# MRFM12B.net
KiCad netlist of a schematic drawn in EAGLE
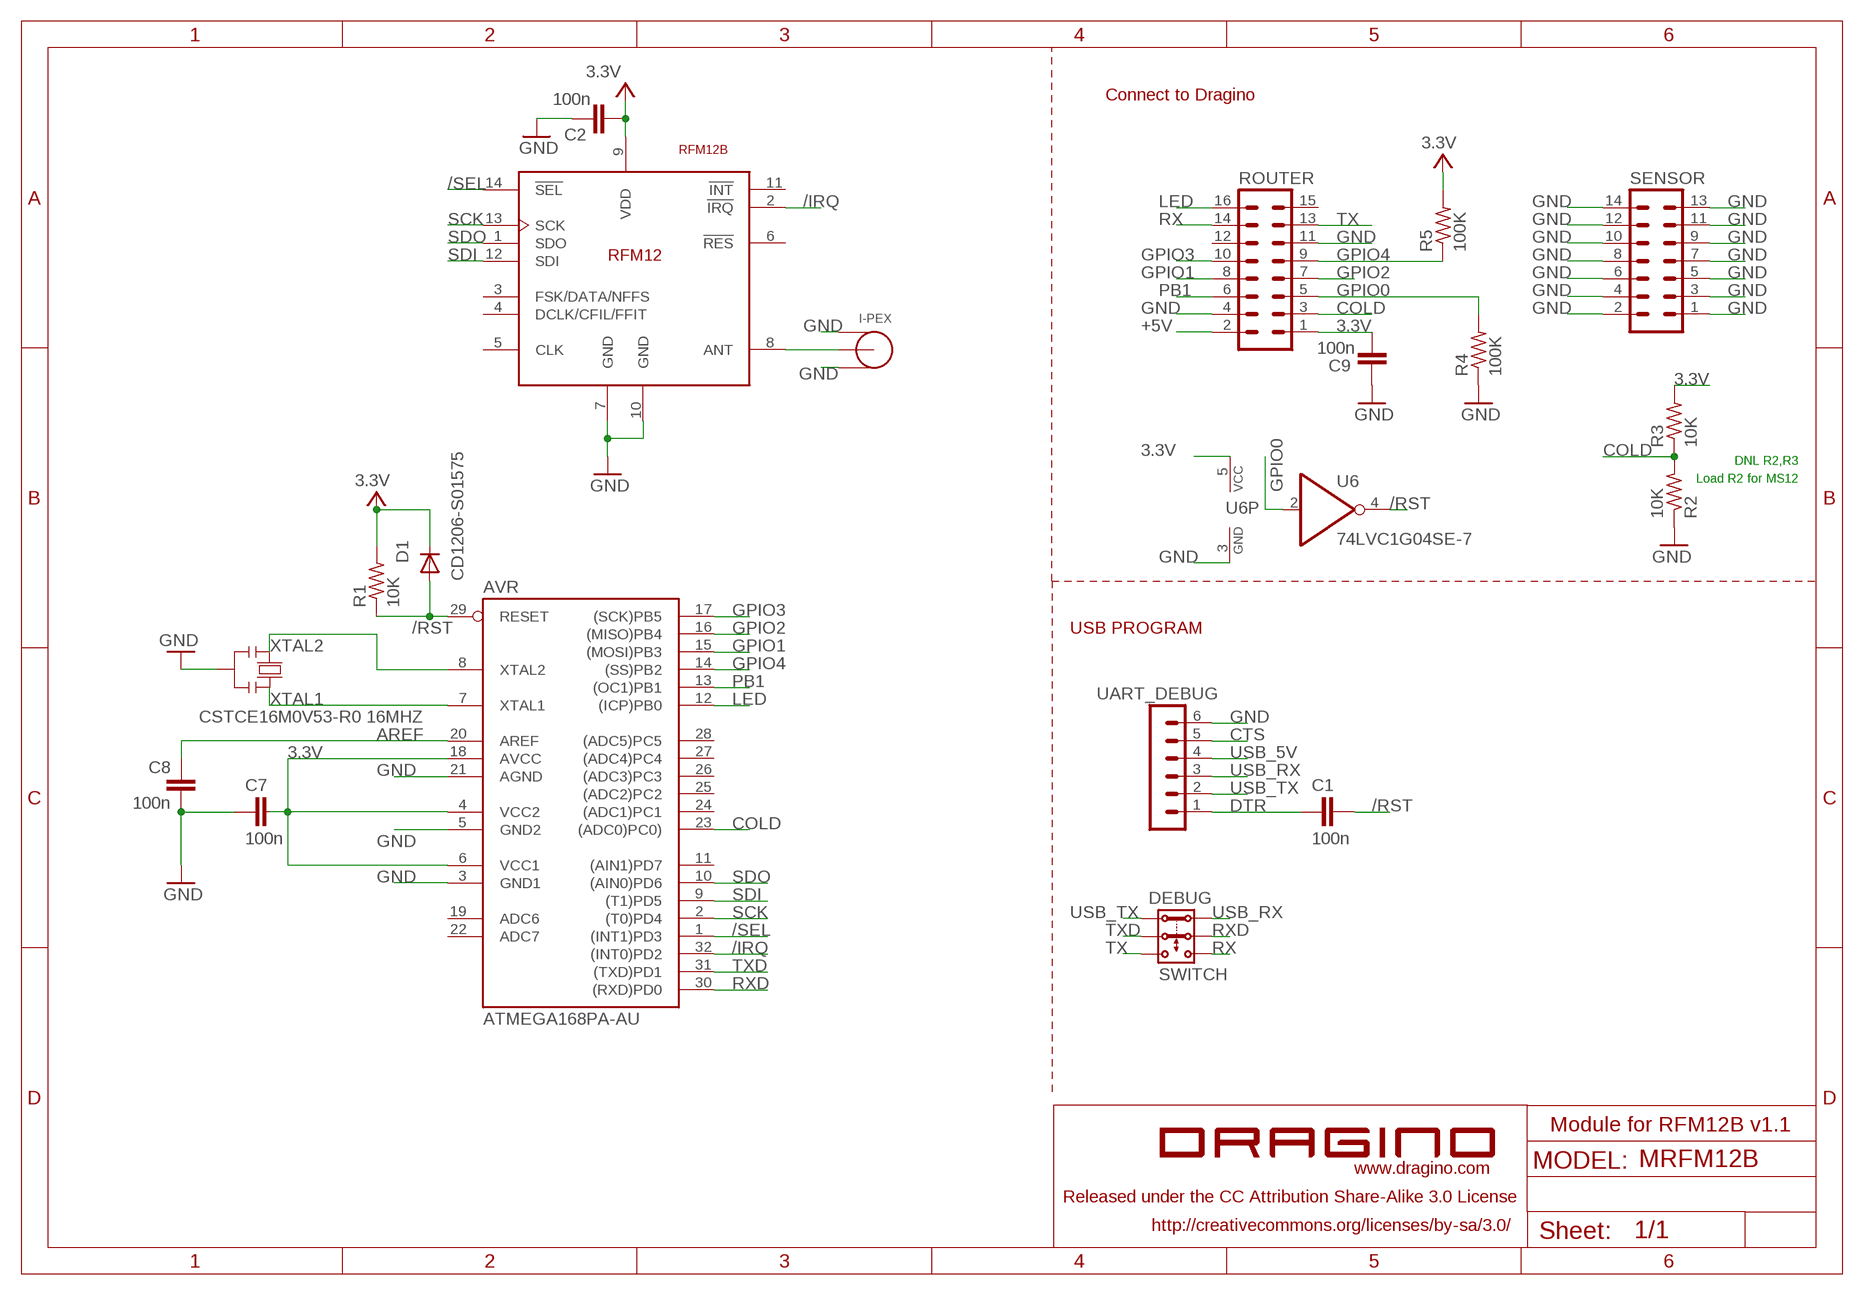
[diagram p0: schematic, sheet 1]

(export (version "E")
  (design (tool "Eeschema 10.0.6"))
  (components
    (comp (ref "AVR")
      (value "ATMEGA168PA-AU")
      (footprint "eagle-import:SMARTPRJ_TQFP32-08")
      (libsource (lib "eagle-import") (part "SMARTPRJ_ATMEGA328P-AU"))
    )
    (comp (ref "C1")
      (value "100n")
      (footprint "eagle-import:C0402")
      (libsource (lib "eagle-import") (part "C-EUC0402"))
    )
    (comp (ref "C2")
      (value "100n")
      (footprint "eagle-import:C0402")
      (libsource (lib "eagle-import") (part "C-EUC0402"))
    )
    (comp (ref "C7")
      (value "100n")
      (footprint "eagle-import:C0402")
      (libsource (lib "eagle-import") (part "C-EUC0402"))
    )
    (comp (ref "C8")
      (value "100n")
      (footprint "eagle-import:C0402")
      (libsource (lib "eagle-import") (part "C-EUC0402"))
    )
    (comp (ref "C9")
      (value "100n")
      (footprint "eagle-import:C0402")
      (libsource (lib "eagle-import") (part "C-EUC0402"))
    )
    (comp (ref "D1")
      (value "CD1206-S01575")
      (footprint "eagle-import:MINIMELF")
      (libsource (lib "eagle-import") (part "DIODE-MINIMELF"))
    )
    (comp (ref "DEBUG")
      (value "SWITCH")
      (footprint "eagle-import:2P2T")
      (libsource (lib "eagle-import") (part "SWITCH-2P2T"))
    )
    (comp (ref "I-PEX")
      (value "I-PEX")
      (footprint "eagle-import:I-PEX")
      (libsource (lib "eagle-import") (part "I-PEX"))
    )
    (comp (ref "R1")
      (value "10K")
      (footprint "eagle-import:R0402")
      (libsource (lib "eagle-import") (part "R-US_R0402"))
    )
    (comp (ref "R2")
      (value "10K")
      (footprint "eagle-import:R0402")
      (libsource (lib "eagle-import") (part "R-US_R0402"))
    )
    (comp (ref "R3")
      (value "10K")
      (footprint "eagle-import:R0402")
      (libsource (lib "eagle-import") (part "R-US_R0402"))
    )
    (comp (ref "R4")
      (value "100K")
      (footprint "eagle-import:R0402")
      (libsource (lib "eagle-import") (part "R-US_R0402"))
    )
    (comp (ref "R5")
      (value "100K")
      (footprint "eagle-import:R0402")
      (libsource (lib "eagle-import") (part "R-US_R0402"))
    )
    (comp (ref "RFM12B")
      (value "RFM12B")
      (footprint "eagle-import:RFM12")
      (libsource (lib "eagle-import") (part "RFM12_SMDSMD"))
    )
    (comp (ref "ROUTER")
      (value "MA08-2")
      (footprint "eagle-import:MA08-2")
      (libsource (lib "eagle-import") (part "MA08-2"))
    )
    (comp (ref "SENSOR")
      (value "MA07-2")
      (footprint "eagle-import:MA07-2")
      (libsource (lib "eagle-import") (part "MA07-2"))
    )
    (comp (ref "U$1")
      (value "LOGO-SILK")
      (footprint "eagle-import:LOGO-SILK-15MM")
      (libsource (lib "eagle-import") (part "LOGO-SILK"))
    )
    (comp (ref "U6")
      (value "74LVC1G04SE-7")
      (footprint "eagle-import:SC70-5")
      (libsource (lib "eagle-import") (part "741G04DCKAHC"))
    )
    (comp (ref "UART_DEBUG")
      (value "MA06-1")
      (footprint "eagle-import:MA06-1")
      (libsource (lib "eagle-import") (part "MA06-1"))
    )
    (comp (ref "Y1")
      (value "CSTCE16M0V53-R0 16MHZ")
      (footprint "eagle-import:RESONATOR")
      (libsource (lib "eagle-import") (part "RESONATORMU"))
    )
  )
  (nets
    (net (code "1") (name "/+5V") (class "Default")
      (node (ref "ROUTER") (pin "2") (pinfunction "2_2") (pintype "passive"))
    )
    (net (code "2") (name "/AREF") (class "Default")
      (node (ref "AVR") (pin "20") (pinfunction "AREF_20") (pintype "passive"))
      (node (ref "C8") (pin "1") (pinfunction "1_1") (pintype "passive"))
    )
    (net (code "3") (name "/COLD") (class "Default")
      (node (ref "AVR") (pin "23") (pinfunction "(ADC0)PC0)_23") (pintype "bidirectional"))
      (node (ref "R2") (pin "2") (pinfunction "2_2") (pintype "passive"))
      (node (ref "R3") (pin "1") (pinfunction "1_1") (pintype "passive"))
      (node (ref "ROUTER") (pin "3") (pinfunction "3_3") (pintype "passive"))
    )
    (net (code "4") (name "/CTS") (class "Default")
      (node (ref "UART_DEBUG") (pin "5") (pinfunction "5_5") (pintype "passive"))
    )
    (net (code "5") (name "/DTR") (class "Default")
      (node (ref "C1") (pin "2") (pinfunction "2_2") (pintype "passive"))
      (node (ref "UART_DEBUG") (pin "1") (pinfunction "1_1") (pintype "passive"))
    )
    (net (code "6") (name "/GPIO0") (class "Default")
      (node (ref "R4") (pin "2") (pinfunction "2_2") (pintype "passive"))
      (node (ref "ROUTER") (pin "5") (pinfunction "5_5") (pintype "passive"))
      (node (ref "U6") (pin "2") (pinfunction "I_2") (pintype "input"))
    )
    (net (code "7") (name "/GPIO1") (class "Default")
      (node (ref "AVR") (pin "15") (pinfunction "(MOSI)PB3_15") (pintype "bidirectional"))
      (node (ref "ROUTER") (pin "8") (pinfunction "8_8") (pintype "passive"))
    )
    (net (code "8") (name "/GPIO2") (class "Default")
      (node (ref "AVR") (pin "16") (pinfunction "(MISO)PB4_16") (pintype "bidirectional"))
      (node (ref "ROUTER") (pin "7") (pinfunction "7_7") (pintype "passive"))
    )
    (net (code "9") (name "/GPIO3") (class "Default")
      (node (ref "AVR") (pin "17") (pinfunction "(SCK)PB5_17") (pintype "bidirectional"))
      (node (ref "ROUTER") (pin "10") (pinfunction "10_10") (pintype "passive"))
    )
    (net (code "10") (name "/GPIO4") (class "Default")
      (node (ref "AVR") (pin "14") (pinfunction "(SS)PB2_14") (pintype "bidirectional"))
      (node (ref "R5") (pin "1") (pinfunction "1_1") (pintype "passive"))
      (node (ref "ROUTER") (pin "9") (pinfunction "9_9") (pintype "passive"))
    )
    (net (code "11") (name "/LED") (class "Default")
      (node (ref "AVR") (pin "12") (pinfunction "(ICP)PB0_12") (pintype "bidirectional"))
      (node (ref "ROUTER") (pin "16") (pinfunction "16_16") (pintype "passive"))
    )
    (net (code "12") (name "/PB1") (class "Default")
      (node (ref "AVR") (pin "13") (pinfunction "(OC1)PB1_13") (pintype "bidirectional"))
      (node (ref "ROUTER") (pin "6") (pinfunction "6_6") (pintype "passive"))
    )
    (net (code "13") (name "/RX") (class "Default")
      (node (ref "DEBUG") (pin "3.1") (pinfunction "3.1_3.1") (pintype "passive"))
      (node (ref "ROUTER") (pin "14") (pinfunction "14_14") (pintype "passive"))
    )
    (net (code "14") (name "/RXD") (class "Default")
      (node (ref "AVR") (pin "30") (pinfunction "(RXD)PD0_30") (pintype "bidirectional"))
      (node (ref "DEBUG") (pin "2.1") (pinfunction "2.1_2.1") (pintype "passive"))
    )
    (net (code "15") (name "/SCK") (class "Default")
      (node (ref "AVR") (pin "2") (pinfunction "(T0)PD4_2") (pintype "bidirectional"))
      (node (ref "RFM12B") (pin "13") (pinfunction "SCK_13") (pintype "input"))
    )
    (net (code "16") (name "/SDI") (class "Default")
      (node (ref "AVR") (pin "9") (pinfunction "(T1)PD5_9") (pintype "bidirectional"))
      (node (ref "RFM12B") (pin "12") (pinfunction "SDI_12") (pintype "input"))
    )
    (net (code "17") (name "/SDO") (class "Default")
      (node (ref "AVR") (pin "10") (pinfunction "(AIN0)PD6_10") (pintype "bidirectional"))
      (node (ref "RFM12B") (pin "1") (pinfunction "SDO_1") (pintype "output"))
    )
    (net (code "18") (name "/TX") (class "Default")
      (node (ref "DEBUG") (pin "3.2") (pinfunction "3.2_3.2") (pintype "passive"))
      (node (ref "ROUTER") (pin "13") (pinfunction "13_13") (pintype "passive"))
    )
    (net (code "19") (name "/TXD") (class "Default")
      (node (ref "AVR") (pin "31") (pinfunction "(TXD)PD1_31") (pintype "bidirectional"))
      (node (ref "DEBUG") (pin "2.2") (pinfunction "2.2_2.2") (pintype "passive"))
    )
    (net (code "20") (name "/USB_5V") (class "Default")
      (node (ref "UART_DEBUG") (pin "4") (pinfunction "4_4") (pintype "passive"))
    )
    (net (code "21") (name "/USB_RX") (class "Default")
      (node (ref "DEBUG") (pin "1.1") (pinfunction "1.1_1.1") (pintype "passive"))
      (node (ref "UART_DEBUG") (pin "3") (pinfunction "3_3") (pintype "passive"))
    )
    (net (code "22") (name "/USB_TX") (class "Default")
      (node (ref "DEBUG") (pin "1.2") (pinfunction "1.2_1.2") (pintype "passive"))
      (node (ref "UART_DEBUG") (pin "2") (pinfunction "2_2") (pintype "passive"))
    )
    (net (code "23") (name "/XTAL1") (class "Default")
      (node (ref "AVR") (pin "7") (pinfunction "XTAL1_7") (pintype "bidirectional"))
      (node (ref "Y1") (pin "3") (pinfunction "3_3") (pintype "passive"))
    )
    (net (code "24") (name "/XTAL2") (class "Default")
      (node (ref "AVR") (pin "8") (pinfunction "XTAL2_8") (pintype "bidirectional"))
      (node (ref "Y1") (pin "1") (pinfunction "1_1") (pintype "passive"))
    )
    (net (code "25") (name "/{slash}IRQ") (class "Default")
      (node (ref "AVR") (pin "32") (pinfunction "(INT0)PD2_32") (pintype "bidirectional"))
      (node (ref "RFM12B") (pin "2") (pinfunction "~{IRQ}_2") (pintype "output"))
    )
    (net (code "26") (name "/{slash}RST") (class "Default")
      (node (ref "AVR") (pin "29") (pinfunction "RESET_29") (pintype "input"))
      (node (ref "C1") (pin "1") (pinfunction "1_1") (pintype "passive"))
      (node (ref "D1") (pin "A") (pinfunction "A_A") (pintype "passive"))
      (node (ref "R1") (pin "1") (pinfunction "1_1") (pintype "passive"))
      (node (ref "U6") (pin "4") (pinfunction "O_4") (pintype "output"))
    )
    (net (code "27") (name "/{slash}SEL") (class "Default")
      (node (ref "AVR") (pin "1") (pinfunction "(INT1)PD3_1") (pintype "bidirectional"))
      (node (ref "RFM12B") (pin "14") (pinfunction "~{SEL}_14") (pintype "input"))
    )
    (net (code "28") (name "3.3V") (class "Default")
      (node (ref "AVR") (pin "18") (pinfunction "AVCC_18") (pintype "power_in"))
      (node (ref "AVR") (pin "4") (pinfunction "VCC2_4") (pintype "power_in"))
      (node (ref "AVR") (pin "6") (pinfunction "VCC1_6") (pintype "power_in"))
      (node (ref "C2") (pin "1") (pinfunction "1_1") (pintype "passive"))
      (node (ref "C7") (pin "1") (pinfunction "1_1") (pintype "passive"))
      (node (ref "C9") (pin "2") (pinfunction "2_2") (pintype "passive"))
      (node (ref "D1") (pin "C") (pinfunction "C_C") (pintype "passive"))
      (node (ref "R1") (pin "2") (pinfunction "2_2") (pintype "passive"))
      (node (ref "R3") (pin "2") (pinfunction "2_2") (pintype "passive"))
      (node (ref "R5") (pin "2") (pinfunction "2_2") (pintype "passive"))
      (node (ref "RFM12B") (pin "9") (pinfunction "VDD_9") (pintype "power_in"))
      (node (ref "ROUTER") (pin "1") (pinfunction "1_1") (pintype "passive"))
      (node (ref "U6") (pin "5") (pinfunction "VCC_5") (pintype "power_in"))
    )
    (net (code "29") (name "GND") (class "Default")
      (node (ref "AVR") (pin "21") (pinfunction "AGND_21") (pintype "power_in"))
      (node (ref "AVR") (pin "3") (pinfunction "GND1_3") (pintype "power_in"))
      (node (ref "AVR") (pin "5") (pinfunction "GND2_5") (pintype "power_in"))
      (node (ref "C2") (pin "2") (pinfunction "2_2") (pintype "passive"))
      (node (ref "C7") (pin "2") (pinfunction "2_2") (pintype "passive"))
      (node (ref "C8") (pin "2") (pinfunction "2_2") (pintype "passive"))
      (node (ref "C9") (pin "1") (pinfunction "1_1") (pintype "passive"))
      (node (ref "I-PEX") (pin "GND") (pinfunction "GND_GND") (pintype "passive"))
      (node (ref "I-PEX") (pin "GND1") (pinfunction "GND1_GND1") (pintype "passive"))
      (node (ref "R2") (pin "1") (pinfunction "1_1") (pintype "passive"))
      (node (ref "R4") (pin "1") (pinfunction "1_1") (pintype "passive"))
      (node (ref "RFM12B") (pin "10") (pinfunction "GND_10") (pintype "passive"))
      (node (ref "RFM12B") (pin "7") (pinfunction "GND_7") (pintype "passive"))
      (node (ref "ROUTER") (pin "11") (pinfunction "11_11") (pintype "passive"))
      (node (ref "ROUTER") (pin "4") (pinfunction "4_4") (pintype "passive"))
      (node (ref "SENSOR") (pin "1") (pinfunction "1_1") (pintype "passive"))
      (node (ref "SENSOR") (pin "10") (pinfunction "10_10") (pintype "passive"))
      (node (ref "SENSOR") (pin "11") (pinfunction "11_11") (pintype "passive"))
      (node (ref "SENSOR") (pin "12") (pinfunction "12_12") (pintype "passive"))
      (node (ref "SENSOR") (pin "13") (pinfunction "13_13") (pintype "passive"))
      (node (ref "SENSOR") (pin "14") (pinfunction "14_14") (pintype "passive"))
      (node (ref "SENSOR") (pin "2") (pinfunction "2_2") (pintype "passive"))
      (node (ref "SENSOR") (pin "3") (pinfunction "3_3") (pintype "passive"))
      (node (ref "SENSOR") (pin "4") (pinfunction "4_4") (pintype "passive"))
      (node (ref "SENSOR") (pin "5") (pinfunction "5_5") (pintype "passive"))
      (node (ref "SENSOR") (pin "6") (pinfunction "6_6") (pintype "passive"))
      (node (ref "SENSOR") (pin "7") (pinfunction "7_7") (pintype "passive"))
      (node (ref "SENSOR") (pin "8") (pinfunction "8_8") (pintype "passive"))
      (node (ref "SENSOR") (pin "9") (pinfunction "9_9") (pintype "passive"))
      (node (ref "U6") (pin "3") (pinfunction "GND_3") (pintype "power_in"))
      (node (ref "UART_DEBUG") (pin "6") (pinfunction "6_6") (pintype "passive"))
      (node (ref "Y1") (pin "2") (pinfunction "2_2") (pintype "passive"))
    )
    (net (code "30") (name "Net-(RFM12B-ANT)") (class "Default")
      (node (ref "I-PEX") (pin "SIG") (pinfunction "SIG_SIG") (pintype "passive"))
      (node (ref "RFM12B") (pin "8") (pinfunction "ANT_8") (pintype "bidirectional"))
    )
    (net (code "31") (name "unconnected-(AVR-(ADC1)PC1-Pad24)") (class "Default")
      (node (ref "AVR") (pin "24") (pinfunction "(ADC1)PC1_24") (pintype "bidirectional"))
    )
    (net (code "32") (name "unconnected-(AVR-(ADC2)PC2-Pad25)") (class "Default")
      (node (ref "AVR") (pin "25") (pinfunction "(ADC2)PC2_25") (pintype "bidirectional"))
    )
    (net (code "33") (name "unconnected-(AVR-(ADC3)PC3-Pad26)") (class "Default")
      (node (ref "AVR") (pin "26") (pinfunction "(ADC3)PC3_26") (pintype "bidirectional"))
    )
    (net (code "34") (name "unconnected-(AVR-(ADC4)PC4-Pad27)") (class "Default")
      (node (ref "AVR") (pin "27") (pinfunction "(ADC4)PC4_27") (pintype "bidirectional"))
    )
    (net (code "35") (name "unconnected-(AVR-(ADC5)PC5-Pad28)") (class "Default")
      (node (ref "AVR") (pin "28") (pinfunction "(ADC5)PC5_28") (pintype "bidirectional"))
    )
    (net (code "36") (name "unconnected-(AVR-(AIN1)PD7-Pad11)") (class "Default")
      (node (ref "AVR") (pin "11") (pinfunction "(AIN1)PD7_11") (pintype "bidirectional"))
    )
    (net (code "37") (name "unconnected-(AVR-ADC6-Pad19)") (class "Default")
      (node (ref "AVR") (pin "19") (pinfunction "ADC6_19") (pintype "bidirectional"))
    )
    (net (code "38") (name "unconnected-(AVR-ADC7-Pad22)") (class "Default")
      (node (ref "AVR") (pin "22") (pinfunction "ADC7_22") (pintype "bidirectional"))
    )
    (net (code "39") (name "unconnected-(RFM12B-CLK-Pad5)") (class "Default")
      (node (ref "RFM12B") (pin "5") (pinfunction "CLK_5") (pintype "output"))
    )
    (net (code "40") (name "unconnected-(RFM12B-DCLK{slash}CFIL{slash}FFIT-Pad4)") (class "Default")
      (node (ref "RFM12B") (pin "4") (pinfunction "DCLK/CFIL/FFIT_4") (pintype "bidirectional"))
    )
    (net (code "41") (name "unconnected-(RFM12B-FSK{slash}DATA{slash}NFFS-Pad3)") (class "Default")
      (node (ref "RFM12B") (pin "3") (pinfunction "FSK/DATA/NFFS_3") (pintype "bidirectional"))
    )
    (net (code "42") (name "unconnected-(RFM12B-~{INT}-Pad11)") (class "Default")
      (node (ref "RFM12B") (pin "11") (pinfunction "~{INT}_11") (pintype "bidirectional"))
    )
    (net (code "43") (name "unconnected-(RFM12B-~{RES}-Pad6)") (class "Default")
      (node (ref "RFM12B") (pin "6") (pinfunction "~{RES}_6") (pintype "bidirectional"))
    )
    (net (code "44") (name "unconnected-(ROUTER-Pad12)") (class "Default")
      (node (ref "ROUTER") (pin "12") (pinfunction "12_12") (pintype "passive"))
    )
    (net (code "45") (name "unconnected-(ROUTER-Pad15)") (class "Default")
      (node (ref "ROUTER") (pin "15") (pinfunction "15_15") (pintype "passive"))
    )
  )
)
